# usb.net
KiCad netlist of a schematic drawn in Altium Designer
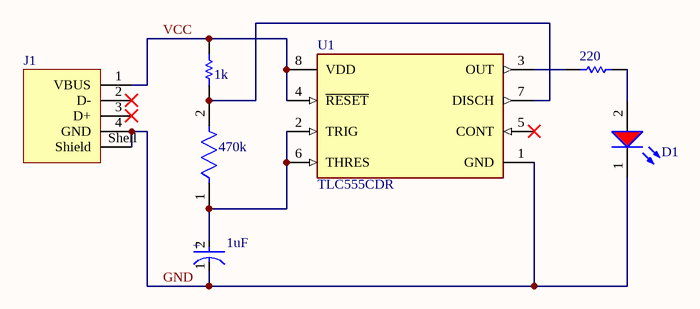
[diagram p0: usb.SchDoc]

(export (version "E")
  (design (tool "Eeschema 10.0.6"))
  (components
    (comp (ref "1k")
      (value "MCRE000140")
      (footprint "RESC0603X26X15ML03T05")
      (fields (field (name "MANUFACTURER") "Multicomp"))
      (libsource (lib "Altium Content Vault") (part "RES"))
    )
    (comp (ref "1uF")
      (value "293D105X0016A2TE3")
      (footprint "FP-293DA-MFG")
      (fields (field (name "TOLERANCE") "20%"))
      (libsource (lib "Altium Content Vault") (part "a00bbbee19879c290e62620ae7e47b1"))
    )
    (comp (ref "220")
      (value "ERJ6ENF2200V")
      (footprint "RESC2013X70X40NL20T20")
      (fields (field (name "MANUFACTURER") "Panasonic"))
      (libsource (lib "Altium Content Vault") (part "RES"))
    )
    (comp (ref "470k")
      (value "CRGCQ1206J470K")
      (footprint "FP-CRGCQ1206-IPC_C")
      (description "CRGCQ1206 470KΩ 0.25W 5% ±100ppm/°C 200V")
      (fields (field (name "MANUFACTURER") "TE Connectivity") (field (name "TOLERANCE") "0.05"))
      (libsource (lib "Altium Content Vault") (part "1029c3af85768c4190bb7ad29bc67b5"))
    )
    (comp (ref "D1")
      (value "150060RS75000")
      (footprint "WL-SMCW_0603_150060xx75000")
      (libsource (lib "Altium Content Vault") (part "LED_Red_2A-1K"))
    )
    (comp (ref "J1")
      (value "61400416021")
      (footprint "61400416021")
      (libsource (lib "Altium Content Vault") (part "USB 2.0_Type A_Receptacle_1 Port"))
    )
    (comp (ref "U1")
      (value "TLC555CDR")
      (footprint "FP-D0008A-IPC_B")
      (description "IC OSC SGL TIMER 2.1MHZ 8-SOIC")
      (libsource (lib "Altium Content Vault") (part "fd1638d23bf5e420a54176ee4f8e783"))
    )
  )
  (nets
    (net (code "1") (name "/GND") (class "Default")
      (node (ref "1uF") (pin "1") (pinfunction "C_1") (pintype "passive"))
      (node (ref "D1") (pin "1") (pinfunction "K_1") (pintype "passive"))
      (node (ref "J1") (pin "4") (pinfunction "GND_4") (pintype "passive"))
      (node (ref "J1") (pin "Shell") (pinfunction "Shield_Shell") (pintype "passive"))
      (node (ref "U1") (pin "1") (pinfunction "GND_1") (pintype "power_in"))
    )
    (net (code "2") (name "/VCC") (class "Default")
      (node (ref "1k") (pin "2") (pinfunction "2_2") (pintype "passive"))
      (node (ref "J1") (pin "1") (pinfunction "VBUS_1") (pintype "passive"))
      (node (ref "U1") (pin "4") (pinfunction "~{RESET}_4") (pintype "input"))
      (node (ref "U1") (pin "8") (pinfunction "VDD_8") (pintype "power_in"))
    )
    (net (code "3") (name "Net-(1uF-A)") (class "Default")
      (node (ref "1uF") (pin "2") (pinfunction "A_2") (pintype "passive"))
      (node (ref "470k") (pin "1") (pinfunction "1_1") (pintype "passive"))
      (node (ref "U1") (pin "2") (pinfunction "TRIG_2") (pintype "input"))
      (node (ref "U1") (pin "6") (pinfunction "THRES_6") (pintype "input"))
    )
    (net (code "4") (name "Net-(D1-A)") (class "Default")
      (node (ref "220") (pin "2") (pinfunction "2_2") (pintype "passive"))
      (node (ref "D1") (pin "2") (pinfunction "A_2") (pintype "passive"))
    )
    (net (code "5") (name "Net-(U1-DISCH)") (class "Default")
      (node (ref "1k") (pin "1") (pinfunction "1_1") (pintype "passive"))
      (node (ref "470k") (pin "2") (pinfunction "2_2") (pintype "passive"))
      (node (ref "U1") (pin "7") (pinfunction "DISCH_7") (pintype "output"))
    )
    (net (code "6") (name "Net-(U1-OUT)") (class "Default")
      (node (ref "220") (pin "1") (pinfunction "1_1") (pintype "passive"))
      (node (ref "U1") (pin "3") (pinfunction "OUT_3") (pintype "output"))
    )
    (net (code "7") (name "unconnected-(J1-D+-Pad3)") (class "Default")
      (node (ref "J1") (pin "3") (pinfunction "D+_3") (pintype "passive+no_connect"))
    )
    (net (code "8") (name "unconnected-(J1-D--Pad2)") (class "Default")
      (node (ref "J1") (pin "2") (pinfunction "D-_2") (pintype "passive+no_connect"))
    )
    (net (code "9") (name "unconnected-(U1-CONT-Pad5)") (class "Default")
      (node (ref "U1") (pin "5") (pinfunction "CONT_5") (pintype "input+no_connect"))
    )
  )
)
